# Base_components.net
KiCad netlist of a schematic drawn in EAGLE
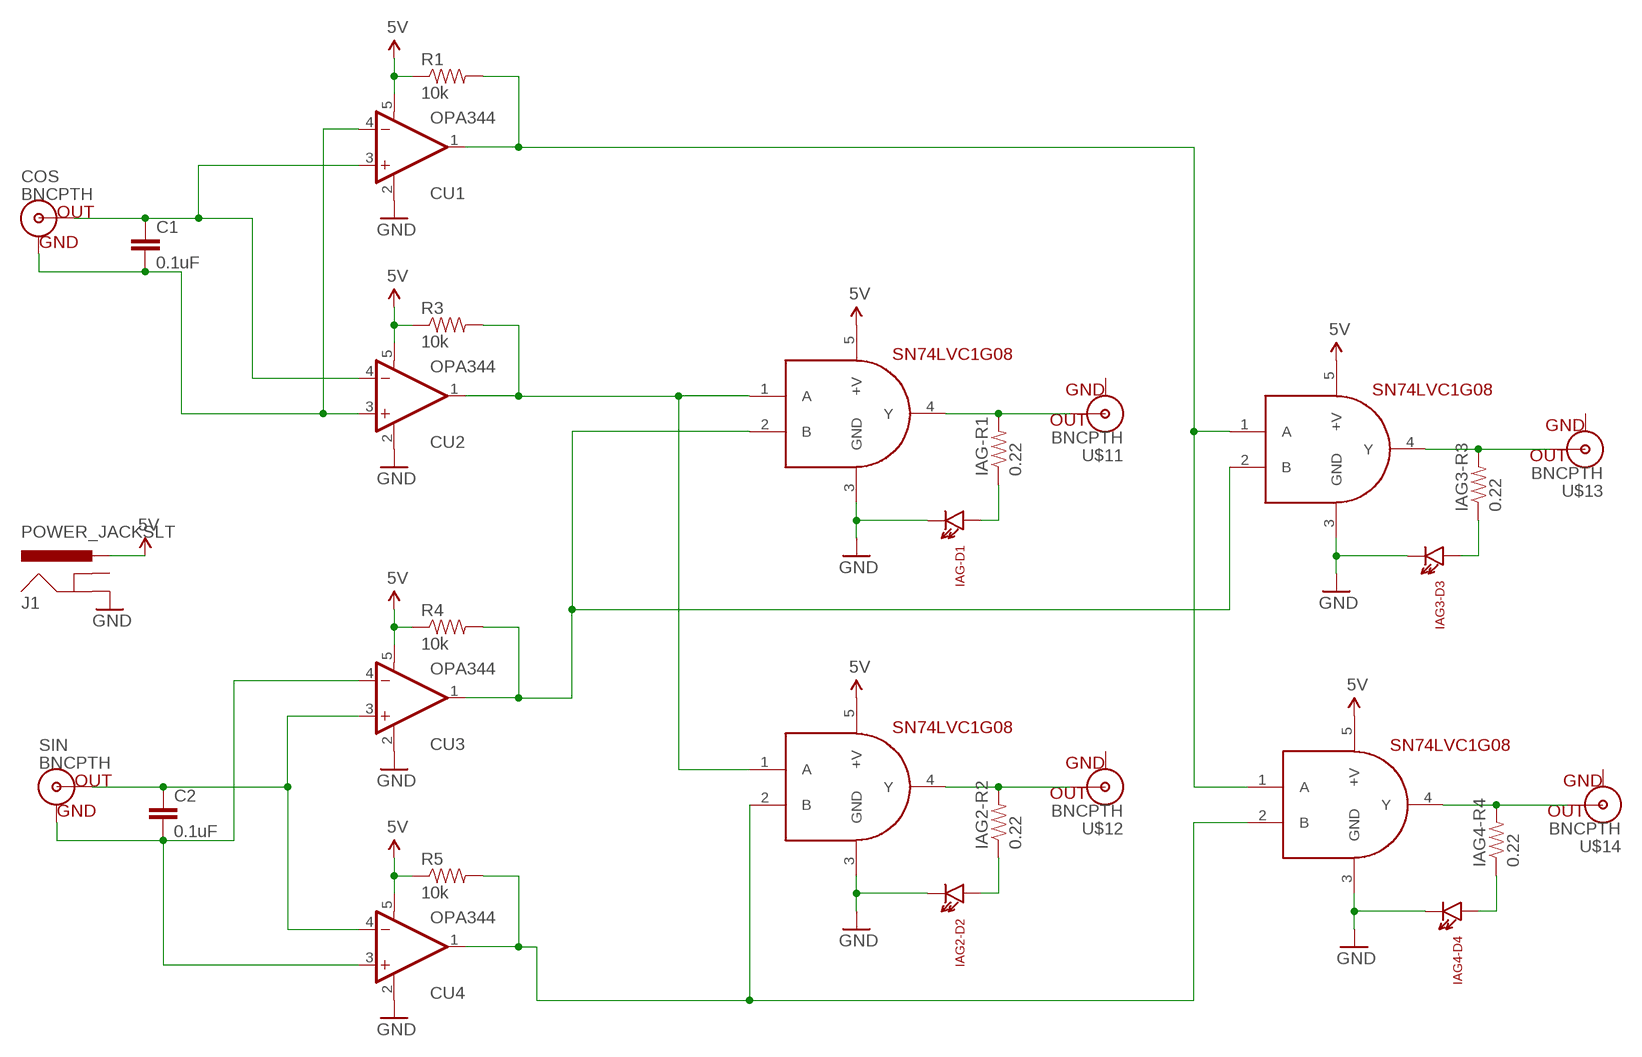
[diagram p0: schematic, sheet 1]

(export (version "E")
  (design (tool "Eeschema 10.0.6"))
  (components
    (comp (ref "C1")
      (value "0.1uF")
      (footprint "eagle-import:0603-CAP")
      (libsource (lib "eagle-import") (part "0.1UF-25V-5%(0603)"))
    )
    (comp (ref "C2")
      (value "0.1uF")
      (footprint "eagle-import:0603-CAP")
      (libsource (lib "eagle-import") (part "0.1UF-25V-5%(0603)"))
    )
    (comp (ref "COS")
      (value "BNCPTH")
      (footprint "eagle-import:BNC")
      (libsource (lib "eagle-import") (part "BNCPTH"))
    )
    (comp (ref "CU1")
      (value "OPA344")
      (footprint "eagle-import:SOT23-5")
      (libsource (lib "eagle-import") (part "OPA344"))
    )
    (comp (ref "CU2")
      (value "OPA344")
      (footprint "eagle-import:SOT23-5")
      (libsource (lib "eagle-import") (part "OPA344"))
    )
    (comp (ref "CU3")
      (value "OPA344")
      (footprint "eagle-import:SOT23-5")
      (libsource (lib "eagle-import") (part "OPA344"))
    )
    (comp (ref "CU4")
      (value "OPA344")
      (footprint "eagle-import:SOT23-5")
      (libsource (lib "eagle-import") (part "OPA344"))
    )
    (comp (ref "IAG-D1")
      (value "LTE-302")
      (footprint "eagle-import:LTE-302")
      (libsource (lib "eagle-import") (part "LTE-302"))
    )
    (comp (ref "IAG-R1")
      (value "0.22")
      (footprint "eagle-import:0805")
      (libsource (lib "eagle-import") (part "0.22OHM1/4W1%(0805)"))
    )
    (comp (ref "IAG1")
      (value "SN74LVC1G08")
      (footprint "eagle-import:SOT23-5")
      (libsource (lib "eagle-import") (part "SN74LVC1G08"))
    )
    (comp (ref "IAG2")
      (value "SN74LVC1G08")
      (footprint "eagle-import:SOT23-5")
      (libsource (lib "eagle-import") (part "SN74LVC1G08"))
    )
    (comp (ref "IAG2-D2")
      (value "LTE-302")
      (footprint "eagle-import:LTE-302")
      (libsource (lib "eagle-import") (part "LTE-302"))
    )
    (comp (ref "IAG2-R2")
      (value "0.22")
      (footprint "eagle-import:0805")
      (libsource (lib "eagle-import") (part "0.22OHM1/4W1%(0805)"))
    )
    (comp (ref "IAG3")
      (value "SN74LVC1G08")
      (footprint "eagle-import:SOT23-5")
      (libsource (lib "eagle-import") (part "SN74LVC1G08"))
    )
    (comp (ref "IAG3-D3")
      (value "LTE-302")
      (footprint "eagle-import:LTE-302")
      (libsource (lib "eagle-import") (part "LTE-302"))
    )
    (comp (ref "IAG3-R3")
      (value "0.22")
      (footprint "eagle-import:0805")
      (libsource (lib "eagle-import") (part "0.22OHM1/4W1%(0805)"))
    )
    (comp (ref "IAG4")
      (value "SN74LVC1G08")
      (footprint "eagle-import:SOT23-5")
      (libsource (lib "eagle-import") (part "SN74LVC1G08"))
    )
    (comp (ref "IAG4-D4")
      (value "LTE-302")
      (footprint "eagle-import:LTE-302")
      (libsource (lib "eagle-import") (part "LTE-302"))
    )
    (comp (ref "IAG4-R4")
      (value "0.22")
      (footprint "eagle-import:0805")
      (libsource (lib "eagle-import") (part "0.22OHM1/4W1%(0805)"))
    )
    (comp (ref "J1")
      (value "POWER_JACKSLT")
      (footprint "eagle-import:POWER_JACK_SLOT")
      (libsource (lib "eagle-import") (part "POWER_JACKSLT"))
    )
    (comp (ref "R1")
      (value "10k")
      (footprint "eagle-import:AXIAL-0.3")
      (libsource (lib "eagle-import") (part "10KOHM-1/4W-1%(PTH)HORIZ"))
    )
    (comp (ref "R3")
      (value "10k")
      (footprint "eagle-import:AXIAL-0.3")
      (libsource (lib "eagle-import") (part "10KOHM-1/4W-1%(PTH)HORIZ"))
    )
    (comp (ref "R4")
      (value "10k")
      (footprint "eagle-import:AXIAL-0.3")
      (libsource (lib "eagle-import") (part "10KOHM-1/4W-1%(PTH)HORIZ"))
    )
    (comp (ref "R5")
      (value "10k")
      (footprint "eagle-import:AXIAL-0.3")
      (libsource (lib "eagle-import") (part "10KOHM-1/4W-1%(PTH)HORIZ"))
    )
    (comp (ref "SIN")
      (value "BNCPTH")
      (footprint "eagle-import:BNC")
      (libsource (lib "eagle-import") (part "BNCPTH"))
    )
    (comp (ref "U$11")
      (value "BNCPTH")
      (footprint "eagle-import:BNC")
      (libsource (lib "eagle-import") (part "BNCPTH"))
    )
    (comp (ref "U$12")
      (value "BNCPTH")
      (footprint "eagle-import:BNC")
      (libsource (lib "eagle-import") (part "BNCPTH"))
    )
    (comp (ref "U$13")
      (value "BNCPTH")
      (footprint "eagle-import:BNC")
      (libsource (lib "eagle-import") (part "BNCPTH"))
    )
    (comp (ref "U$14")
      (value "BNCPTH")
      (footprint "eagle-import:BNC")
      (libsource (lib "eagle-import") (part "BNCPTH"))
    )
  )
  (nets
    (net (code "1") (name "5V") (class "Default")
      (node (ref "CU1") (pin "5") (pinfunction "V+_5") (pintype "power_in"))
      (node (ref "CU2") (pin "5") (pinfunction "V+_5") (pintype "power_in"))
      (node (ref "CU3") (pin "5") (pinfunction "V+_5") (pintype "power_in"))
      (node (ref "CU4") (pin "5") (pinfunction "V+_5") (pintype "power_in"))
      (node (ref "IAG1") (pin "5") (pinfunction "+V_5") (pintype "bidirectional"))
      (node (ref "IAG2") (pin "5") (pinfunction "+V_5") (pintype "bidirectional"))
      (node (ref "IAG3") (pin "5") (pinfunction "+V_5") (pintype "bidirectional"))
      (node (ref "IAG4") (pin "5") (pinfunction "+V_5") (pintype "bidirectional"))
      (node (ref "J1") (pin "PWR") (pinfunction "PWR_PWR") (pintype "bidirectional"))
      (node (ref "R1") (pin "P$1") (pinfunction "1_P$1") (pintype "passive"))
      (node (ref "R3") (pin "P$1") (pinfunction "1_P$1") (pintype "passive"))
      (node (ref "R4") (pin "P$1") (pinfunction "1_P$1") (pintype "passive"))
      (node (ref "R5") (pin "P$1") (pinfunction "1_P$1") (pintype "passive"))
    )
    (net (code "2") (name "GND") (class "Default")
      (node (ref "CU1") (pin "2") (pinfunction "V-_2") (pintype "power_in"))
      (node (ref "CU2") (pin "2") (pinfunction "V-_2") (pintype "power_in"))
      (node (ref "CU3") (pin "2") (pinfunction "V-_2") (pintype "power_in"))
      (node (ref "CU4") (pin "2") (pinfunction "V-_2") (pintype "power_in"))
      (node (ref "IAG-D1") (pin "C") (pinfunction "C_C") (pintype "bidirectional"))
      (node (ref "IAG1") (pin "3") (pinfunction "GND_3") (pintype "bidirectional"))
      (node (ref "IAG2") (pin "3") (pinfunction "GND_3") (pintype "bidirectional"))
      (node (ref "IAG2-D2") (pin "C") (pinfunction "C_C") (pintype "bidirectional"))
      (node (ref "IAG3") (pin "3") (pinfunction "GND_3") (pintype "bidirectional"))
      (node (ref "IAG3-D3") (pin "C") (pinfunction "C_C") (pintype "bidirectional"))
      (node (ref "IAG4") (pin "3") (pinfunction "GND_3") (pintype "bidirectional"))
      (node (ref "IAG4-D4") (pin "C") (pinfunction "C_C") (pintype "bidirectional"))
      (node (ref "J1") (pin "GND@2") (pinfunction "GND_GND@2") (pintype "bidirectional"))
    )
    (net (code "3") (name "Net-(COS-OUT)") (class "Default")
      (node (ref "C1") (pin "1") (pinfunction "1_1") (pintype "passive"))
      (node (ref "COS") (pin "S") (pinfunction "OUT_S") (pintype "bidirectional"))
      (node (ref "CU1") (pin "3") (pinfunction "+IN_3") (pintype "input"))
      (node (ref "CU2") (pin "4") (pinfunction "-IN_4") (pintype "input"))
    )
    (net (code "4") (name "Net-(CU1--IN)") (class "Default")
      (node (ref "C1") (pin "2") (pinfunction "2_2") (pintype "passive"))
      (node (ref "COS") (pin "GND") (pinfunction "GND_GND") (pintype "bidirectional"))
      (node (ref "CU1") (pin "4") (pinfunction "-IN_4") (pintype "input"))
      (node (ref "CU2") (pin "3") (pinfunction "+IN_3") (pintype "input"))
    )
    (net (code "5") (name "Net-(CU1-OUT)") (class "Default")
      (node (ref "CU1") (pin "1") (pinfunction "OUT_1") (pintype "output"))
      (node (ref "IAG3") (pin "1") (pinfunction "A_1") (pintype "bidirectional"))
      (node (ref "IAG4") (pin "1") (pinfunction "A_1") (pintype "bidirectional"))
      (node (ref "R1") (pin "P$2") (pinfunction "2_P$2") (pintype "passive"))
    )
    (net (code "6") (name "Net-(CU2-OUT)") (class "Default")
      (node (ref "CU2") (pin "1") (pinfunction "OUT_1") (pintype "output"))
      (node (ref "IAG1") (pin "1") (pinfunction "A_1") (pintype "bidirectional"))
      (node (ref "IAG2") (pin "1") (pinfunction "A_1") (pintype "bidirectional"))
      (node (ref "R3") (pin "P$2") (pinfunction "2_P$2") (pintype "passive"))
    )
    (net (code "7") (name "Net-(CU3-+IN)") (class "Default")
      (node (ref "C2") (pin "1") (pinfunction "1_1") (pintype "passive"))
      (node (ref "CU3") (pin "3") (pinfunction "+IN_3") (pintype "input"))
      (node (ref "CU4") (pin "4") (pinfunction "-IN_4") (pintype "input"))
      (node (ref "SIN") (pin "S") (pinfunction "OUT_S") (pintype "bidirectional"))
    )
    (net (code "8") (name "Net-(CU3--IN)") (class "Default")
      (node (ref "C2") (pin "2") (pinfunction "2_2") (pintype "passive"))
      (node (ref "CU3") (pin "4") (pinfunction "-IN_4") (pintype "input"))
      (node (ref "CU4") (pin "3") (pinfunction "+IN_3") (pintype "input"))
      (node (ref "SIN") (pin "GND") (pinfunction "GND_GND") (pintype "bidirectional"))
    )
    (net (code "9") (name "Net-(CU3-OUT)") (class "Default")
      (node (ref "CU3") (pin "1") (pinfunction "OUT_1") (pintype "output"))
      (node (ref "IAG1") (pin "2") (pinfunction "B_2") (pintype "bidirectional"))
      (node (ref "IAG3") (pin "2") (pinfunction "B_2") (pintype "bidirectional"))
      (node (ref "R4") (pin "P$2") (pinfunction "2_P$2") (pintype "passive"))
    )
    (net (code "10") (name "Net-(CU4-OUT)") (class "Default")
      (node (ref "CU4") (pin "1") (pinfunction "OUT_1") (pintype "output"))
      (node (ref "IAG2") (pin "2") (pinfunction "B_2") (pintype "bidirectional"))
      (node (ref "IAG4") (pin "2") (pinfunction "B_2") (pintype "bidirectional"))
      (node (ref "R5") (pin "P$2") (pinfunction "2_P$2") (pintype "passive"))
    )
    (net (code "11") (name "Net-(IAG-D1-PadA)") (class "Default")
      (node (ref "IAG-D1") (pin "A") (pinfunction "A_A") (pintype "bidirectional"))
      (node (ref "IAG-R1") (pin "1") (pinfunction "1_1") (pintype "passive"))
    )
    (net (code "12") (name "Net-(IAG1-Y)") (class "Default")
      (node (ref "IAG-R1") (pin "2") (pinfunction "2_2") (pintype "passive"))
      (node (ref "IAG1") (pin "4") (pinfunction "Y_4") (pintype "bidirectional"))
      (node (ref "U$11") (pin "S") (pinfunction "OUT_S") (pintype "bidirectional"))
    )
    (net (code "13") (name "Net-(IAG2-D2-PadA)") (class "Default")
      (node (ref "IAG2-D2") (pin "A") (pinfunction "A_A") (pintype "bidirectional"))
      (node (ref "IAG2-R2") (pin "1") (pinfunction "1_1") (pintype "passive"))
    )
    (net (code "14") (name "Net-(IAG2-Y)") (class "Default")
      (node (ref "IAG2") (pin "4") (pinfunction "Y_4") (pintype "bidirectional"))
      (node (ref "IAG2-R2") (pin "2") (pinfunction "2_2") (pintype "passive"))
      (node (ref "U$12") (pin "S") (pinfunction "OUT_S") (pintype "bidirectional"))
    )
    (net (code "15") (name "Net-(IAG3-D3-PadA)") (class "Default")
      (node (ref "IAG3-D3") (pin "A") (pinfunction "A_A") (pintype "bidirectional"))
      (node (ref "IAG3-R3") (pin "1") (pinfunction "1_1") (pintype "passive"))
    )
    (net (code "16") (name "Net-(IAG3-Y)") (class "Default")
      (node (ref "IAG3") (pin "4") (pinfunction "Y_4") (pintype "bidirectional"))
      (node (ref "IAG3-R3") (pin "2") (pinfunction "2_2") (pintype "passive"))
      (node (ref "U$13") (pin "S") (pinfunction "OUT_S") (pintype "bidirectional"))
    )
    (net (code "17") (name "Net-(IAG4-D4-PadA)") (class "Default")
      (node (ref "IAG4-D4") (pin "A") (pinfunction "A_A") (pintype "bidirectional"))
      (node (ref "IAG4-R4") (pin "1") (pinfunction "1_1") (pintype "passive"))
    )
    (net (code "18") (name "Net-(IAG4-Y)") (class "Default")
      (node (ref "IAG4") (pin "4") (pinfunction "Y_4") (pintype "bidirectional"))
      (node (ref "IAG4-R4") (pin "2") (pinfunction "2_2") (pintype "passive"))
      (node (ref "U$14") (pin "S") (pinfunction "OUT_S") (pintype "bidirectional"))
    )
    (net (code "19") (name "unconnected-(J1-GNDBREAK-PadGND@1)") (class "Default")
      (node (ref "J1") (pin "GND@1") (pinfunction "GNDBREAK_GND@1") (pintype "bidirectional"))
    )
    (net (code "20") (name "unconnected-(U$11-PadGND)") (class "Default")
      (node (ref "U$11") (pin "GND") (pinfunction "GND_GND") (pintype "bidirectional"))
    )
    (net (code "21") (name "unconnected-(U$12-PadGND)") (class "Default")
      (node (ref "U$12") (pin "GND") (pinfunction "GND_GND") (pintype "bidirectional"))
    )
    (net (code "22") (name "unconnected-(U$13-PadGND)") (class "Default")
      (node (ref "U$13") (pin "GND") (pinfunction "GND_GND") (pintype "bidirectional"))
    )
    (net (code "23") (name "unconnected-(U$14-PadGND)") (class "Default")
      (node (ref "U$14") (pin "GND") (pinfunction "GND_GND") (pintype "bidirectional"))
    )
  )
)
